# PowerSection.net
KiCad netlist of a schematic drawn in Altium Designer
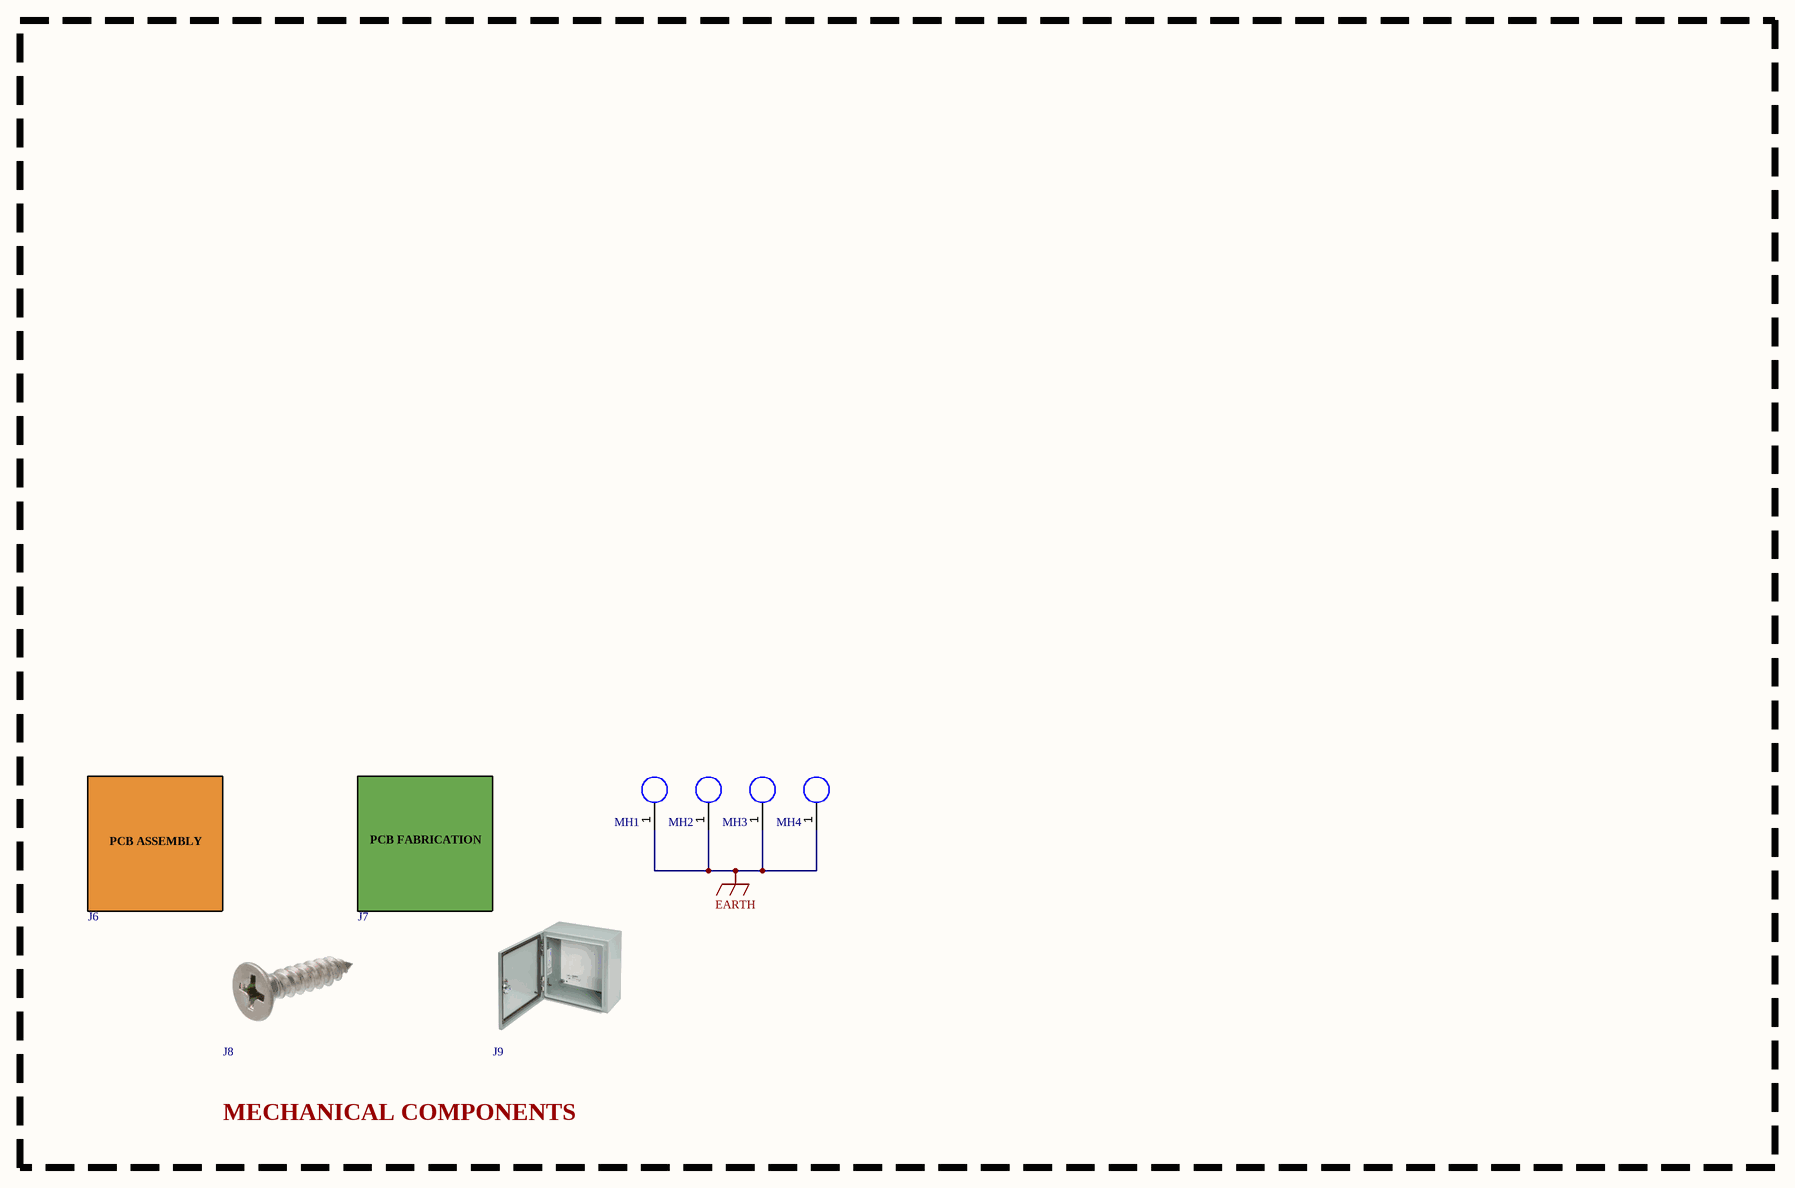
[diagram p0: PowerSection.SchDoc]

(export (version "E")
  (design (tool "Eeschema 10.0.6"))
  (components
    (comp (ref "J6") (value "APCB") (description "Assembled PCB") (libsource (lib "Jumper") (part "APCB")))
    (comp (ref "J7") (value "BPCB") (description "Bare PCB") (libsource (lib "Jumper") (part "BPCB")))
    (comp (ref "J8") (value "SCREW") (description "Mounting Screw") (libsource (lib "Jumper") (part "SCREW")))
    (comp (ref "J9")
      (value "ENCLOSURE")
      (description "PCB Enclosure")
      (libsource (lib "Jumper") (part "ENCLOSURE"))
    )
    (comp (ref "MH1")
      (value "MountingHole4X6")
      (footprint "MountingHole4X6")
      (libsource (lib "Jumper") (part "MountingHole4X6"))
    )
    (comp (ref "MH2")
      (value "MountingHole4X6")
      (footprint "MountingHole4X6")
      (libsource (lib "Jumper") (part "MountingHole4X6"))
    )
    (comp (ref "MH3")
      (value "MountingHole4X6")
      (footprint "MountingHole4X6")
      (libsource (lib "Jumper") (part "MountingHole4X6"))
    )
    (comp (ref "MH4")
      (value "MountingHole4X6")
      (footprint "MountingHole4X6")
      (libsource (lib "Jumper") (part "MountingHole4X6"))
    )
  )
  (nets
    (net (code "1") (name "EARTH") (class "Default")
      (node (ref "MH1") (pin "1") (pinfunction "1_1") (pintype "passive"))
      (node (ref "MH2") (pin "1") (pinfunction "1_1") (pintype "passive"))
      (node (ref "MH3") (pin "1") (pinfunction "1_1") (pintype "passive"))
      (node (ref "MH4") (pin "1") (pinfunction "1_1") (pintype "passive"))
    )
  )
)
